# dss_v3.net
KiCad netlist of a schematic drawn in EAGLE
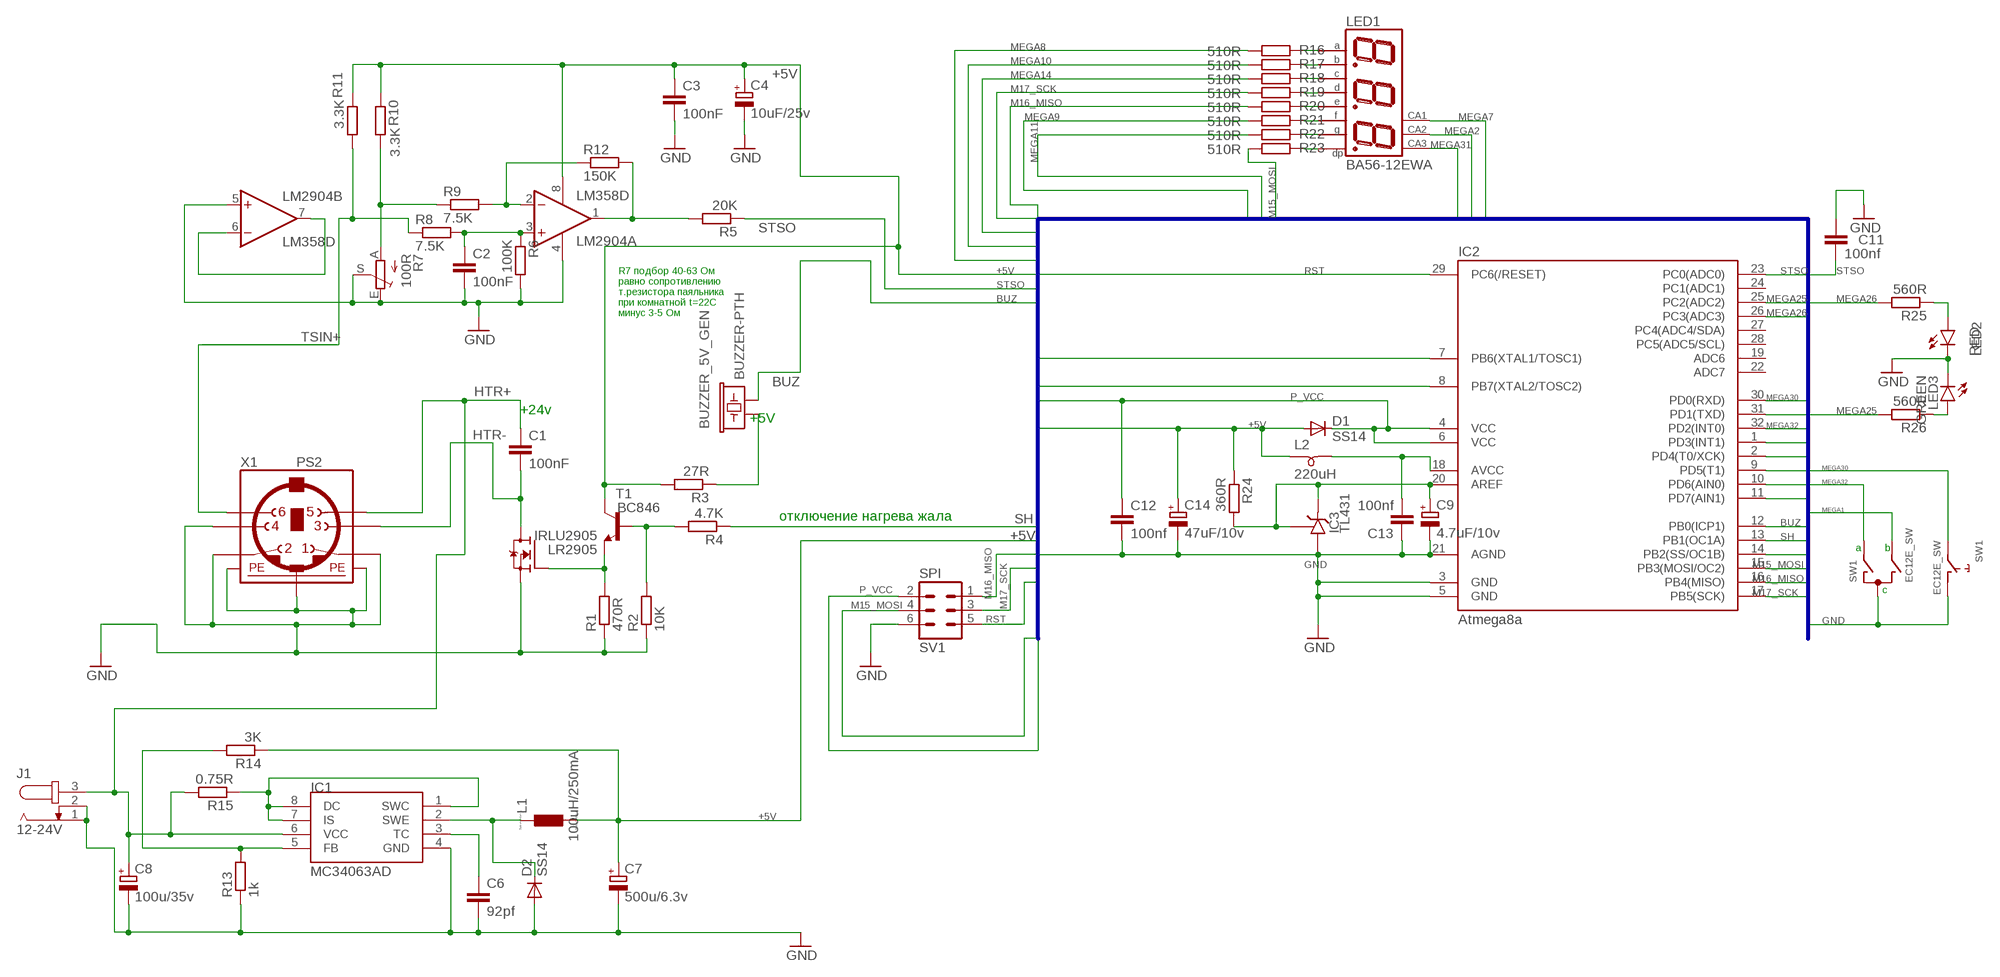
[diagram p0: schematic, sheet 1]

(export (version "E")
  (design (tool "Eeschema 10.0.6"))
  (components
    (comp (ref "BUZZER_5V_GEN")
      (value "BUZZER-PTH")
      (footprint "eagle-import:BUZZER-12MM")
      (libsource (lib "eagle-import") (part "BUZZER-PTH"))
    )
    (comp (ref "C1")
      (value "100nF")
      (footprint "eagle-import:C0805")
      (libsource (lib "eagle-import") (part "C-EUC0805"))
    )
    (comp (ref "C2")
      (value "100nF")
      (footprint "eagle-import:C0805")
      (libsource (lib "eagle-import") (part "C-EUC0805"))
    )
    (comp (ref "C3")
      (value "100nF")
      (footprint "eagle-import:C0805")
      (libsource (lib "eagle-import") (part "C-EUC0805"))
    )
    (comp (ref "C4")
      (value "10uF/25v")
      (footprint "eagle-import:CT6032")
      (libsource (lib "eagle-import") (part "CPOL-EUCT6032"))
    )
    (comp (ref "C6")
      (value "92pf")
      (footprint "eagle-import:C0805")
      (libsource (lib "eagle-import") (part "C-EUC0805"))
    )
    (comp (ref "C7")
      (value "500u/6.3v")
      (footprint "eagle-import:E3,5-8")
      (libsource (lib "eagle-import") (part "CPOL-EUE3.5-8"))
    )
    (comp (ref "C8")
      (value "100u/35v")
      (footprint "eagle-import:E3,5-8")
      (libsource (lib "eagle-import") (part "CPOL-EUE3.5-8"))
    )
    (comp (ref "C9")
      (value "4.7uF/10v")
      (footprint "eagle-import:CT3216")
      (libsource (lib "eagle-import") (part "CPOL-EUCT3216"))
    )
    (comp (ref "C11")
      (value "100nf")
      (footprint "eagle-import:C0805")
      (libsource (lib "eagle-import") (part "C-EUC0805"))
    )
    (comp (ref "C12")
      (value "100nf")
      (footprint "eagle-import:C0805")
      (libsource (lib "eagle-import") (part "C-EUC0805"))
    )
    (comp (ref "C13")
      (value "100nf")
      (footprint "eagle-import:C0805")
      (libsource (lib "eagle-import") (part "C-EUC0805"))
    )
    (comp (ref "C14")
      (value "47uF/10v")
      (footprint "eagle-import:CT3528")
      (libsource (lib "eagle-import") (part "CPOL-EUCT3528"))
    )
    (comp (ref "D1")
      (value "SS14")
      (footprint "eagle-import:DO214AC")
      (libsource (lib "eagle-import") (part "DIODE-DO214AC"))
    )
    (comp (ref "D2")
      (value "SS14")
      (footprint "eagle-import:DO214AC")
      (libsource (lib "eagle-import") (part "DIODE-DO214AC"))
    )
    (comp (ref "IC1")
      (value "MC34063AD")
      (footprint "eagle-import:SOIC8")
      (libsource (lib "eagle-import") (part "MC34063AD"))
    )
    (comp (ref "IC2")
      (value "Atmega8a")
      (footprint "eagle-import:TQFP32-08")
      (libsource (lib "eagle-import") (part "ATMEGA8-AU"))
    )
    (comp (ref "IC3")
      (value "TL431")
      (footprint "eagle-import:SOT23")
      (libsource (lib "eagle-import") (part "TL431CLPSOT23"))
    )
    (comp (ref "IRLU2905")
      (value "LR2905")
      (footprint "eagle-import:TO252")
      (libsource (lib "eagle-import") (part "SPW47N60S5"))
    )
    (comp (ref "J1")
      (value "12-24V")
      (footprint "eagle-import:SPC4077")
      (libsource (lib "eagle-import") (part "JACK-PLUG0"))
    )
    (comp (ref "L1")
      (value "100uH/250mA")
      (footprint "eagle-import:L4532P")
      (libsource (lib "eagle-import") (part "LL4532P"))
    )
    (comp (ref "L2")
      (value "220uH")
      (footprint "eagle-import:SM-B5")
      (libsource (lib "eagle-import") (part "SM-B5"))
    )
    (comp (ref "LED1")
      (value "BA56-12EWA")
      (footprint "eagle-import:BX56-12")
      (libsource (lib "eagle-import") (part "B?56-12WAAE"))
    )
    (comp (ref "LED2")
      (value "RED")
      (footprint "eagle-import:CHIP-LED0805")
      (libsource (lib "eagle-import") (part "LEDCHIP-LED0805"))
    )
    (comp (ref "LED3")
      (value "GREEN")
      (footprint "eagle-import:CHIP-LED0805")
      (libsource (lib "eagle-import") (part "LEDCHIP-LED0805"))
    )
    (comp (ref "LM2904")
      (value "LM358D")
      (footprint "eagle-import:SO08")
      (libsource (lib "eagle-import") (part "LM358D"))
    )
    (comp (ref "R1")
      (value "470R")
      (footprint "eagle-import:R0805")
      (libsource (lib "eagle-import") (part "R-EU_R0805"))
    )
    (comp (ref "R2")
      (value "10K")
      (footprint "eagle-import:R0805")
      (libsource (lib "eagle-import") (part "R-EU_R0805"))
    )
    (comp (ref "R3")
      (value "27R")
      (footprint "eagle-import:R0805")
      (libsource (lib "eagle-import") (part "R-EU_R0805"))
    )
    (comp (ref "R4")
      (value "4.7K")
      (footprint "eagle-import:R0805")
      (libsource (lib "eagle-import") (part "R-EU_R0805"))
    )
    (comp (ref "R5")
      (value "20K")
      (footprint "eagle-import:R0805")
      (libsource (lib "eagle-import") (part "R-EU_R0805"))
    )
    (comp (ref "R6")
      (value "100K")
      (footprint "eagle-import:R0805")
      (libsource (lib "eagle-import") (part "R-EU_R0805"))
    )
    (comp (ref "R7")
      (value "100R")
      (footprint "eagle-import:B25P")
      (libsource (lib "eagle-import") (part "TRIM_EU-B25P"))
    )
    (comp (ref "R8")
      (value "7.5K")
      (footprint "eagle-import:R0805")
      (libsource (lib "eagle-import") (part "R-EU_R0805"))
    )
    (comp (ref "R9")
      (value "7.5K")
      (footprint "eagle-import:R0805")
      (libsource (lib "eagle-import") (part "R-EU_R0805"))
    )
    (comp (ref "R10")
      (value "3.3K")
      (footprint "eagle-import:R0805")
      (libsource (lib "eagle-import") (part "R-EU_R0805"))
    )
    (comp (ref "R11")
      (value "3.3K")
      (footprint "eagle-import:R0805")
      (libsource (lib "eagle-import") (part "R-EU_R0805"))
    )
    (comp (ref "R12")
      (value "150K")
      (footprint "eagle-import:R0805")
      (libsource (lib "eagle-import") (part "R-EU_R0805"))
    )
    (comp (ref "R13")
      (value "1k")
      (footprint "eagle-import:R0805")
      (libsource (lib "eagle-import") (part "R-EU_R0805"))
    )
    (comp (ref "R14")
      (value "3K")
      (footprint "eagle-import:R0805")
      (libsource (lib "eagle-import") (part "R-EU_R0805"))
    )
    (comp (ref "R15")
      (value "0.75R")
      (footprint "eagle-import:R0805")
      (libsource (lib "eagle-import") (part "R-EU_R0805"))
    )
    (comp (ref "R16")
      (value "510R")
      (footprint "eagle-import:R0805")
      (libsource (lib "eagle-import") (part "R-EU_R0805"))
    )
    (comp (ref "R17")
      (value "510R")
      (footprint "eagle-import:R0805")
      (libsource (lib "eagle-import") (part "R-EU_R0805"))
    )
    (comp (ref "R18")
      (value "510R")
      (footprint "eagle-import:R0805")
      (libsource (lib "eagle-import") (part "R-EU_R0805"))
    )
    (comp (ref "R19")
      (value "510R")
      (footprint "eagle-import:R0805")
      (libsource (lib "eagle-import") (part "R-EU_R0805"))
    )
    (comp (ref "R20")
      (value "510R")
      (footprint "eagle-import:R0805")
      (libsource (lib "eagle-import") (part "R-EU_R0805"))
    )
    (comp (ref "R21")
      (value "510R")
      (footprint "eagle-import:R0805")
      (libsource (lib "eagle-import") (part "R-EU_R0805"))
    )
    (comp (ref "R22")
      (value "510R")
      (footprint "eagle-import:R0805")
      (libsource (lib "eagle-import") (part "R-EU_R0805"))
    )
    (comp (ref "R23")
      (value "510R")
      (footprint "eagle-import:R0805")
      (libsource (lib "eagle-import") (part "R-EU_R0805"))
    )
    (comp (ref "R24")
      (value "360R")
      (footprint "eagle-import:R0805")
      (libsource (lib "eagle-import") (part "R-EU_R0805"))
    )
    (comp (ref "R25")
      (value "560R")
      (footprint "eagle-import:R0805")
      (libsource (lib "eagle-import") (part "R-EU_R0805"))
    )
    (comp (ref "R26")
      (value "560R")
      (footprint "eagle-import:R0805")
      (libsource (lib "eagle-import") (part "R-EU_R0805"))
    )
    (comp (ref "SV1")
      (value "SPI")
      (footprint "eagle-import:ML6")
      (libsource (lib "eagle-import") (part "ML6"))
    )
    (comp (ref "SW1")
      (value "EC12E_SW")
      (footprint "eagle-import:ALPS_EC12E_SW")
      (fields (field (name "MPN") "EC12E2424407"))
      (libsource (lib "eagle-import") (part "EC12E_SW"))
    )
    (comp (ref "T1")
      (value "BC846")
      (footprint "eagle-import:SOT23")
      (libsource (lib "eagle-import") (part "BC846"))
    )
    (comp (ref "X1")
      (value "PS2")
      (footprint "eagle-import:M_DIN6")
      (libsource (lib "eagle-import") (part "MINI_DIN_6"))
    )
  )
  (nets
    (net (code "1") (name "/+5V") (class "Default")
      (node (ref "C14") (pin "+") (pinfunction "+_+") (pintype "passive"))
      (node (ref "C3") (pin "1") (pinfunction "1_1") (pintype "passive"))
      (node (ref "C4") (pin "+") (pinfunction "+_+") (pintype "passive"))
      (node (ref "C7") (pin "+") (pinfunction "+_+") (pintype "passive"))
      (node (ref "D1") (pin "A") (pinfunction "A_A") (pintype "passive"))
      (node (ref "L1") (pin "2") (pinfunction "2_2") (pintype "passive"))
      (node (ref "L2") (pin "1") (pinfunction "1_1") (pintype "passive"))
      (node (ref "LM2904") (pin "8") (pinfunction "V+_8") (pintype "power_in"))
      (node (ref "R10") (pin "1") (pinfunction "1_1") (pintype "passive"))
      (node (ref "R11") (pin "1") (pinfunction "1_1") (pintype "passive"))
      (node (ref "R14") (pin "1") (pinfunction "1_1") (pintype "passive"))
      (node (ref "R24") (pin "1") (pinfunction "1_1") (pintype "passive"))
      (node (ref "R3") (pin "2") (pinfunction "2_2") (pintype "passive"))
      (node (ref "T1") (pin "3") (pinfunction "C_3") (pintype "passive"))
    )
    (net (code "2") (name "/BUZ") (class "Default")
      (node (ref "BUZZER_5V_GEN") (pin "-") (pinfunction "2_-") (pintype "passive"))
      (node (ref "IC2") (pin "12") (pinfunction "PB0(ICP1)_12") (pintype "bidirectional"))
    )
    (net (code "3") (name "/HTR+") (class "Default")
      (node (ref "C1") (pin "1") (pinfunction "1_1") (pintype "passive"))
      (node (ref "C8") (pin "+") (pinfunction "+_+") (pintype "passive"))
      (node (ref "IC1") (pin "6") (pinfunction "VCC_6") (pintype "passive"))
      (node (ref "J1") (pin "3") (pinfunction "3_3") (pintype "passive"))
      (node (ref "R15") (pin "2") (pinfunction "2_2") (pintype "passive"))
      (node (ref "X1") (pin "6") (pinfunction "6_6") (pintype "passive"))
    )
    (net (code "4") (name "/HTR-") (class "Default")
      (node (ref "C1") (pin "2") (pinfunction "2_2") (pintype "passive"))
      (node (ref "IRLU2905") (pin "4") (pinfunction "D_4") (pintype "passive"))
      (node (ref "X1") (pin "3") (pinfunction "3_3") (pintype "passive"))
    )
    (net (code "5") (name "/M15_MOSI") (class "Default")
      (node (ref "IC2") (pin "15") (pinfunction "PB3(MOSI/OC2)_15") (pintype "bidirectional"))
      (node (ref "R23") (pin "2") (pinfunction "2_2") (pintype "passive"))
      (node (ref "SV1") (pin "4") (pinfunction "4_4") (pintype "passive"))
    )
    (net (code "6") (name "/M16_MISO") (class "Default")
      (node (ref "IC2") (pin "16") (pinfunction "PB4(MISO)_16") (pintype "bidirectional"))
      (node (ref "R20") (pin "2") (pinfunction "2_2") (pintype "passive"))
      (node (ref "SV1") (pin "1") (pinfunction "1_1") (pintype "passive"))
    )
    (net (code "7") (name "/M17_SCK") (class "Default")
      (node (ref "IC2") (pin "17") (pinfunction "PB5(SCK)_17") (pintype "bidirectional"))
      (node (ref "R19") (pin "2") (pinfunction "2_2") (pintype "passive"))
      (node (ref "SV1") (pin "3") (pinfunction "3_3") (pintype "passive"))
    )
    (net (code "8") (name "/MEGA1") (class "Default")
      (node (ref "IC2") (pin "1") (pinfunction "PD3(INT1)_1") (pintype "bidirectional"))
      (node (ref "SW1") (pin "B") (pinfunction "B_B") (pintype "passive"))
    )
    (net (code "9") (name "/MEGA2") (class "Default")
      (node (ref "IC2") (pin "2") (pinfunction "PD4(T0/XCK)_2") (pintype "bidirectional"))
      (node (ref "LED1") (pin "9") (pinfunction "CA_9") (pintype "passive"))
    )
    (net (code "10") (name "/MEGA7") (class "Default")
      (node (ref "IC2") (pin "7") (pinfunction "PB6(XTAL1/TOSC1)_7") (pintype "bidirectional"))
      (node (ref "LED1") (pin "12") (pinfunction "CA_12") (pintype "passive"))
    )
    (net (code "11") (name "/MEGA8") (class "Default")
      (node (ref "IC2") (pin "8") (pinfunction "PB7(XTAL2/TOSC2)_8") (pintype "bidirectional"))
      (node (ref "R16") (pin "2") (pinfunction "2_2") (pintype "passive"))
    )
    (net (code "12") (name "/MEGA9") (class "Default")
      (node (ref "IC2") (pin "9") (pinfunction "PD5(T1)_9") (pintype "bidirectional"))
      (node (ref "R21") (pin "2") (pinfunction "2_2") (pintype "passive"))
    )
    (net (code "13") (name "/MEGA10") (class "Default")
      (node (ref "IC2") (pin "10") (pinfunction "PD6(AIN0)_10") (pintype "bidirectional"))
      (node (ref "R17") (pin "2") (pinfunction "2_2") (pintype "passive"))
    )
    (net (code "14") (name "/MEGA11") (class "Default")
      (node (ref "IC2") (pin "11") (pinfunction "PD7(AIN1)_11") (pintype "bidirectional"))
      (node (ref "R22") (pin "2") (pinfunction "2_2") (pintype "passive"))
    )
    (net (code "15") (name "/MEGA14") (class "Default")
      (node (ref "IC2") (pin "14") (pinfunction "PB2(SS/OC1B)_14") (pintype "bidirectional"))
      (node (ref "R18") (pin "2") (pinfunction "2_2") (pintype "passive"))
    )
    (net (code "16") (name "/MEGA25") (class "Default")
      (node (ref "IC2") (pin "25") (pinfunction "PC2(ADC2)_25") (pintype "bidirectional"))
      (node (ref "R26") (pin "2") (pinfunction "2_2") (pintype "passive"))
    )
    (net (code "17") (name "/MEGA26") (class "Default")
      (node (ref "IC2") (pin "26") (pinfunction "PC3(ADC3)_26") (pintype "bidirectional"))
      (node (ref "R25") (pin "2") (pinfunction "2_2") (pintype "passive"))
    )
    (net (code "18") (name "/MEGA30") (class "Default")
      (node (ref "IC2") (pin "30") (pinfunction "PD0(RXD)_30") (pintype "bidirectional"))
      (node (ref "SW1") (pin "E") (pinfunction "2_E") (pintype "passive"))
    )
    (net (code "19") (name "/MEGA31") (class "Default")
      (node (ref "IC2") (pin "31") (pinfunction "PD1(TXD)_31") (pintype "bidirectional"))
      (node (ref "LED1") (pin "8") (pinfunction "CA_8") (pintype "passive"))
    )
    (net (code "20") (name "/MEGA32") (class "Default")
      (node (ref "IC2") (pin "32") (pinfunction "PD2(INT0)_32") (pintype "bidirectional"))
      (node (ref "SW1") (pin "A") (pinfunction "A_A") (pintype "passive"))
    )
    (net (code "21") (name "/P_VCC") (class "Default")
      (node (ref "C12") (pin "1") (pinfunction "1_1") (pintype "passive"))
      (node (ref "D1") (pin "C") (pinfunction "C_C") (pintype "passive"))
      (node (ref "IC2") (pin "4") (pinfunction "VCC_4") (pintype "power_in"))
      (node (ref "IC2") (pin "6") (pinfunction "VCC_6") (pintype "power_in"))
      (node (ref "SV1") (pin "2") (pinfunction "2_2") (pintype "passive"))
    )
    (net (code "22") (name "/RST") (class "Default")
      (node (ref "IC2") (pin "29") (pinfunction "PC6(/RESET)_29") (pintype "bidirectional"))
      (node (ref "SV1") (pin "5") (pinfunction "5_5") (pintype "passive"))
    )
    (net (code "23") (name "/SH") (class "Default")
      (node (ref "IC2") (pin "13") (pinfunction "PB1(OC1A)_13") (pintype "bidirectional"))
      (node (ref "R4") (pin "1") (pinfunction "1_1") (pintype "passive"))
    )
    (net (code "24") (name "/STSO") (class "Default")
      (node (ref "C11") (pin "2") (pinfunction "2_2") (pintype "passive"))
      (node (ref "IC2") (pin "23") (pinfunction "PC0(ADC0)_23") (pintype "bidirectional"))
      (node (ref "R5") (pin "1") (pinfunction "1_1") (pintype "passive"))
    )
    (net (code "25") (name "/TSIN+") (class "Default")
      (node (ref "R11") (pin "2") (pinfunction "2_2") (pintype "passive"))
      (node (ref "R8") (pin "1") (pinfunction "1_1") (pintype "passive"))
      (node (ref "X1") (pin "8") (pinfunction "8_8") (pintype "passive"))
    )
    (net (code "26") (name "GND") (class "Default")
      (node (ref "C11") (pin "1") (pinfunction "1_1") (pintype "passive"))
      (node (ref "C12") (pin "2") (pinfunction "2_2") (pintype "passive"))
      (node (ref "C13") (pin "1") (pinfunction "1_1") (pintype "passive"))
      (node (ref "C14") (pin "-") (pinfunction "-_-") (pintype "passive"))
      (node (ref "C2") (pin "2") (pinfunction "2_2") (pintype "passive"))
      (node (ref "C3") (pin "2") (pinfunction "2_2") (pintype "passive"))
      (node (ref "C4") (pin "-") (pinfunction "-_-") (pintype "passive"))
      (node (ref "C6") (pin "2") (pinfunction "2_2") (pintype "passive"))
      (node (ref "C7") (pin "-") (pinfunction "-_-") (pintype "passive"))
      (node (ref "C8") (pin "-") (pinfunction "-_-") (pintype "passive"))
      (node (ref "C9") (pin "-") (pinfunction "-_-") (pintype "passive"))
      (node (ref "D2") (pin "A") (pinfunction "A_A") (pintype "passive"))
      (node (ref "IC1") (pin "4") (pinfunction "GND_4") (pintype "passive"))
      (node (ref "IC2") (pin "21") (pinfunction "AGND_21") (pintype "power_in"))
      (node (ref "IC2") (pin "3") (pinfunction "GND_3") (pintype "power_in"))
      (node (ref "IC2") (pin "5") (pinfunction "GND_5") (pintype "power_in"))
      (node (ref "IC3") (pin "3") (pinfunction "A_3") (pintype "passive"))
      (node (ref "IRLU2905") (pin "3") (pinfunction "S_3") (pintype "passive"))
      (node (ref "J1") (pin "1") (pinfunction "1_1") (pintype "passive"))
      (node (ref "J1") (pin "2") (pinfunction "2_2") (pintype "passive"))
      (node (ref "LED2") (pin "C") (pinfunction "C_C") (pintype "passive"))
      (node (ref "LED3") (pin "C") (pinfunction "C_C") (pintype "passive"))
      (node (ref "LM2904") (pin "4") (pinfunction "V-_4") (pintype "power_in"))
      (node (ref "LM2904") (pin "5") (pinfunction "+IN_5") (pintype "input"))
      (node (ref "R1") (pin "1") (pinfunction "1_1") (pintype "passive"))
      (node (ref "R13") (pin "1") (pinfunction "1_1") (pintype "passive"))
      (node (ref "R2") (pin "1") (pinfunction "1_1") (pintype "passive"))
      (node (ref "R6") (pin "2") (pinfunction "2_2") (pintype "passive"))
      (node (ref "R7") (pin "E") (pinfunction "E_E") (pintype "passive"))
      (node (ref "R7") (pin "S") (pinfunction "S_S") (pintype "passive"))
      (node (ref "SV1") (pin "6") (pinfunction "6_6") (pintype "passive"))
      (node (ref "SW1") (pin "C") (pinfunction "C_C") (pintype "passive"))
      (node (ref "SW1") (pin "D") (pinfunction "1_D") (pintype "passive"))
      (node (ref "X1") (pin "1") (pinfunction "1_1") (pintype "passive"))
      (node (ref "X1") (pin "2") (pinfunction "2_2") (pintype "passive"))
      (node (ref "X1") (pin "5") (pinfunction "5_5") (pintype "passive"))
      (node (ref "X1") (pin "SH1") (pinfunction "PE1_SH1") (pintype "power_in"))
      (node (ref "X1") (pin "SH2") (pinfunction "PE2_SH2") (pintype "power_in"))
      (node (ref "X1") (pin "SH3") (pinfunction "PE3_SH3") (pintype "power_in"))
    )
    (net (code "27") (name "Net-(BUZZER_5V_GEN-1)") (class "Default")
      (node (ref "BUZZER_5V_GEN") (pin "+") (pinfunction "1_+") (pintype "passive"))
      (node (ref "R3") (pin "1") (pinfunction "1_1") (pintype "passive"))
    )
    (net (code "28") (name "Net-(IC1-DC)") (class "Default")
      (node (ref "IC1") (pin "1") (pinfunction "SWC_1") (pintype "passive"))
      (node (ref "IC1") (pin "7") (pinfunction "IS_7") (pintype "passive"))
      (node (ref "IC1") (pin "8") (pinfunction "DC_8") (pintype "passive"))
      (node (ref "R15") (pin "1") (pinfunction "1_1") (pintype "passive"))
    )
    (net (code "29") (name "Net-(IC1-FB)") (class "Default")
      (node (ref "IC1") (pin "5") (pinfunction "FB_5") (pintype "passive"))
      (node (ref "R13") (pin "2") (pinfunction "2_2") (pintype "passive"))
      (node (ref "R14") (pin "2") (pinfunction "2_2") (pintype "passive"))
    )
    (net (code "30") (name "Net-(IC1-SWE)") (class "Default")
      (node (ref "D2") (pin "C") (pinfunction "C_C") (pintype "passive"))
      (node (ref "IC1") (pin "2") (pinfunction "SWE_2") (pintype "passive"))
      (node (ref "L1") (pin "1") (pinfunction "1_1") (pintype "passive"))
    )
    (net (code "31") (name "Net-(IC1-TC)") (class "Default")
      (node (ref "C6") (pin "1") (pinfunction "1_1") (pintype "passive"))
      (node (ref "IC1") (pin "3") (pinfunction "TC_3") (pintype "passive"))
    )
    (net (code "32") (name "Net-(IC2-AREF)") (class "Default")
      (node (ref "C9") (pin "+") (pinfunction "+_+") (pintype "passive"))
      (node (ref "IC2") (pin "20") (pinfunction "AREF_20") (pintype "passive"))
      (node (ref "IC3") (pin "1") (pinfunction "C_1") (pintype "passive"))
      (node (ref "IC3") (pin "2") (pinfunction "R_2") (pintype "passive"))
      (node (ref "R24") (pin "2") (pinfunction "2_2") (pintype "passive"))
    )
    (net (code "33") (name "Net-(IC2-AVCC)") (class "Default")
      (node (ref "C13") (pin "2") (pinfunction "2_2") (pintype "passive"))
      (node (ref "IC2") (pin "18") (pinfunction "AVCC_18") (pintype "passive"))
      (node (ref "L2") (pin "2") (pinfunction "2_2") (pintype "passive"))
    )
    (net (code "34") (name "Net-(IRLU2905-G)") (class "Default")
      (node (ref "IRLU2905") (pin "1") (pinfunction "G_1") (pintype "passive"))
      (node (ref "R1") (pin "2") (pinfunction "2_2") (pintype "passive"))
      (node (ref "T1") (pin "2") (pinfunction "E_2") (pintype "passive"))
    )
    (net (code "35") (name "Net-(LED1-A)") (class "Default")
      (node (ref "LED1") (pin "11") (pinfunction "A_11") (pintype "passive"))
      (node (ref "R16") (pin "1") (pinfunction "1_1") (pintype "passive"))
    )
    (net (code "36") (name "Net-(LED1-B)") (class "Default")
      (node (ref "LED1") (pin "7") (pinfunction "B_7") (pintype "passive"))
      (node (ref "R17") (pin "1") (pinfunction "1_1") (pintype "passive"))
    )
    (net (code "37") (name "Net-(LED1-C)") (class "Default")
      (node (ref "LED1") (pin "4") (pinfunction "C_4") (pintype "passive"))
      (node (ref "R18") (pin "1") (pinfunction "1_1") (pintype "passive"))
    )
    (net (code "38") (name "Net-(LED1-D)") (class "Default")
      (node (ref "LED1") (pin "2") (pinfunction "D_2") (pintype "passive"))
      (node (ref "R19") (pin "1") (pinfunction "1_1") (pintype "passive"))
    )
    (net (code "39") (name "Net-(LED1-DP)") (class "Default")
      (node (ref "LED1") (pin "3") (pinfunction "DP_3") (pintype "passive"))
      (node (ref "R23") (pin "1") (pinfunction "1_1") (pintype "passive"))
    )
    (net (code "40") (name "Net-(LED1-E)") (class "Default")
      (node (ref "LED1") (pin "1") (pinfunction "E_1") (pintype "passive"))
      (node (ref "R20") (pin "1") (pinfunction "1_1") (pintype "passive"))
    )
    (net (code "41") (name "Net-(LED1-F)") (class "Default")
      (node (ref "LED1") (pin "10") (pinfunction "F_10") (pintype "passive"))
      (node (ref "R21") (pin "1") (pinfunction "1_1") (pintype "passive"))
    )
    (net (code "42") (name "Net-(LED1-G)") (class "Default")
      (node (ref "LED1") (pin "5") (pinfunction "G_5") (pintype "passive"))
      (node (ref "R22") (pin "1") (pinfunction "1_1") (pintype "passive"))
    )
    (net (code "43") (name "Net-(LED2-PadA)") (class "Default")
      (node (ref "LED2") (pin "A") (pinfunction "A_A") (pintype "passive"))
      (node (ref "R25") (pin "1") (pinfunction "1_1") (pintype "passive"))
    )
    (net (code "44") (name "Net-(LED3-PadA)") (class "Default")
      (node (ref "LED3") (pin "A") (pinfunction "A_A") (pintype "passive"))
      (node (ref "R26") (pin "1") (pinfunction "1_1") (pintype "passive"))
    )
    (net (code "45") (name "Net-(LM2904A-+IN)") (class "Default")
      (node (ref "C2") (pin "1") (pinfunction "1_1") (pintype "passive"))
      (node (ref "LM2904") (pin "3") (pinfunction "+IN_3") (pintype "input"))
      (node (ref "R6") (pin "1") (pinfunction "1_1") (pintype "passive"))
      (node (ref "R8") (pin "2") (pinfunction "2_2") (pintype "passive"))
    )
    (net (code "46") (name "Net-(LM2904A--IN)") (class "Default")
      (node (ref "LM2904") (pin "2") (pinfunction "-IN_2") (pintype "input"))
      (node (ref "R12") (pin "1") (pinfunction "1_1") (pintype "passive"))
      (node (ref "R9") (pin "2") (pinfunction "2_2") (pintype "passive"))
    )
    (net (code "47") (name "Net-(LM2904A-OUT)") (class "Default")
      (node (ref "LM2904") (pin "1") (pinfunction "OUT_1") (pintype "output"))
      (node (ref "R12") (pin "2") (pinfunction "2_2") (pintype "passive"))
      (node (ref "R5") (pin "2") (pinfunction "2_2") (pintype "passive"))
    )
    (net (code "48") (name "Net-(LM2904B--IN)") (class "Default")
      (node (ref "LM2904") (pin "6") (pinfunction "-IN_6") (pintype "input"))
      (node (ref "LM2904") (pin "7") (pinfunction "OUT_7") (pintype "output"))
    )
    (net (code "49") (name "Net-(R10-Pad2)") (class "Default")
      (node (ref "R10") (pin "2") (pinfunction "2_2") (pintype "passive"))
      (node (ref "R7") (pin "A") (pinfunction "A_A") (pintype "passive"))
      (node (ref "R9") (pin "1") (pinfunction "1_1") (pintype "passive"))
    )
    (net (code "50") (name "Net-(T1-B)") (class "Default")
      (node (ref "R2") (pin "2") (pinfunction "2_2") (pintype "passive"))
      (node (ref "R4") (pin "2") (pinfunction "2_2") (pintype "passive"))
      (node (ref "T1") (pin "1") (pinfunction "B_1") (pintype "passive"))
    )
    (net (code "51") (name "unconnected-(IC2-ADC6-Pad19)") (class "Default")
      (node (ref "IC2") (pin "19") (pinfunction "ADC6_19") (pintype "passive"))
    )
    (net (code "52") (name "unconnected-(IC2-ADC7-Pad22)") (class "Default")
      (node (ref "IC2") (pin "22") (pinfunction "ADC7_22") (pintype "passive"))
    )
    (net (code "53") (name "unconnected-(IC2-PC1(ADC1)-Pad24)") (class "Default")
      (node (ref "IC2") (pin "24") (pinfunction "PC1(ADC1)_24") (pintype "bidirectional"))
    )
    (net (code "54") (name "unconnected-(IC2-PC4(ADC4{slash}SDA)-Pad27)") (class "Default")
      (node (ref "IC2") (pin "27") (pinfunction "PC4(ADC4/SDA)_27") (pintype "bidirectional"))
    )
    (net (code "55") (name "unconnected-(IC2-PC5(ADC5{slash}SCL)-Pad28)") (class "Default")
      (node (ref "IC2") (pin "28") (pinfunction "PC5(ADC5/SCL)_28") (pintype "bidirectional"))
    )
  )
)
